# NeoJointV2A-000.net
KiCad netlist of a schematic drawn in EAGLE
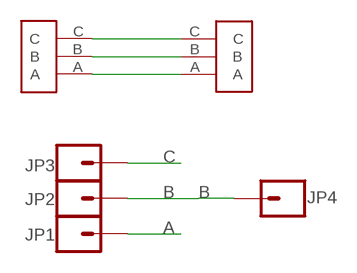
[diagram p0: schematic, sheet 1]

(export (version "E")
  (design (tool "Eeschema 10.0.6"))
  (components
    (comp (ref "JP1")
      (value "M01PTH")
      (footprint "eagle-import:1X01")
      (libsource (lib "eagle-import") (part "M01PTH"))
    )
    (comp (ref "JP2")
      (value "M01PTH")
      (footprint "eagle-import:1X01")
      (libsource (lib "eagle-import") (part "M01PTH"))
    )
    (comp (ref "JP3")
      (value "M01PTH")
      (footprint "eagle-import:1X01")
      (libsource (lib "eagle-import") (part "M01PTH"))
    )
    (comp (ref "JP4")
      (value "M01PTH")
      (footprint "eagle-import:1X01")
      (libsource (lib "eagle-import") (part "M01PTH"))
    )
    (comp (ref "U$1")
      (value "LED_STRIP_3P")
      (footprint "eagle-import:LEDSTRIP-3P")
      (libsource (lib "eagle-import") (part "LED_STRIP_3P"))
    )
    (comp (ref "U$2")
      (value "LED_STRIP_3P")
      (footprint "eagle-import:LEDSTRIP-3P")
      (libsource (lib "eagle-import") (part "LED_STRIP_3P"))
    )
  )
  (nets
    (net (code "1") (name "/A") (class "Default")
      (node (ref "JP1") (pin "1") (pinfunction "1_1") (pintype "passive"))
      (node (ref "U$1") (pin "A") (pinfunction "A_A") (pintype "bidirectional"))
      (node (ref "U$2") (pin "A") (pinfunction "A_A") (pintype "bidirectional"))
    )
    (net (code "2") (name "/B") (class "Default")
      (node (ref "JP2") (pin "1") (pinfunction "1_1") (pintype "passive"))
      (node (ref "JP4") (pin "1") (pinfunction "1_1") (pintype "passive"))
      (node (ref "U$1") (pin "B") (pinfunction "B_B") (pintype "bidirectional"))
      (node (ref "U$2") (pin "B") (pinfunction "B_B") (pintype "bidirectional"))
    )
    (net (code "3") (name "/C") (class "Default")
      (node (ref "JP3") (pin "1") (pinfunction "1_1") (pintype "passive"))
      (node (ref "U$1") (pin "C") (pinfunction "C_C") (pintype "bidirectional"))
      (node (ref "U$2") (pin "C") (pinfunction "C_C") (pintype "bidirectional"))
    )
  )
)
